# BANK_3.net
KiCad netlist of a schematic drawn in Altium Designer
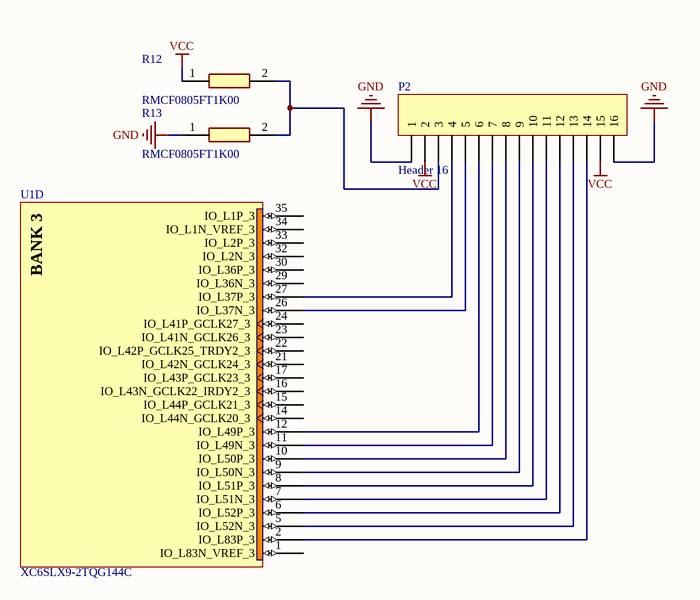
[diagram p0: BANK_3.SchDoc]

(export (version "E")
  (design (tool "Eeschema 10.0.6"))
  (components
    (comp (ref "P2")
      (value "Header 16")
      (footprint "HDR1X16")
      (description "Header, 16-Pin")
      (fields (field (name "PUBLISHER") "Altium Limited"))
      (libsource (lib "Schlib1_FPGA") (part "Header 16"))
    )
    (comp (ref "R12")
      (value "RMCF0805FT1K00")
      (footprint "PcbLib1:RESC2012X65N")
      (description "Resistor")
      (fields (field (name "MF") "Stackpole Electronics Inc"))
      (libsource (lib "Schlib1_FPGA") (part "RES 1K OHM 1% 1/8W 0805"))
    )
    (comp (ref "R13")
      (value "RMCF0805FT1K00")
      (footprint "PcbLib1:RESC2012X65N")
      (description "Resistor")
      (fields (field (name "MF") "Stackpole Electronics Inc"))
      (libsource (lib "Schlib1_FPGA") (part "RES 1K OHM 1% 1/8W 0805"))
    )
    (comp (ref "U1")
      (value "XC6SLX9-2TQG144C")
      (footprint "TQG144_N")
      (libsource (lib "Xilinx Spartan-6") (part "XC6SLX9-2TQG144C"))
    )
  )
  (nets
    (net (code "1") (name "GND") (class "Default")
      (node (ref "P2") (pin "1") (pinfunction "1_1") (pintype "passive"))
      (node (ref "P2") (pin "16") (pinfunction "16_16") (pintype "passive"))
      (node (ref "R13") (pin "1") (pinfunction "1_1") (pintype "passive"))
    )
    (net (code "2") (name "Net-(P2-Pad3)") (class "Default")
      (node (ref "P2") (pin "3") (pinfunction "3_3") (pintype "passive"))
      (node (ref "R12") (pin "2") (pinfunction "2_2") (pintype "passive"))
      (node (ref "R13") (pin "2") (pinfunction "2_2") (pintype "passive"))
    )
    (net (code "3") (name "Net-(U1D-IO_L37N_3)") (class "Default")
      (node (ref "P2") (pin "5") (pinfunction "5_5") (pintype "passive"))
      (node (ref "U1") (pin "26") (pinfunction "IO_L37N_3_26") (pintype "bidirectional"))
    )
    (net (code "4") (name "Net-(U1D-IO_L37P_3)") (class "Default")
      (node (ref "P2") (pin "4") (pinfunction "4_4") (pintype "passive"))
      (node (ref "U1") (pin "27") (pinfunction "IO_L37P_3_27") (pintype "bidirectional"))
    )
    (net (code "5") (name "Net-(U1D-IO_L49N_3)") (class "Default")
      (node (ref "P2") (pin "7") (pinfunction "7_7") (pintype "passive"))
      (node (ref "U1") (pin "11") (pinfunction "IO_L49N_3_11") (pintype "bidirectional"))
    )
    (net (code "6") (name "Net-(U1D-IO_L49P_3)") (class "Default")
      (node (ref "P2") (pin "6") (pinfunction "6_6") (pintype "passive"))
      (node (ref "U1") (pin "12") (pinfunction "IO_L49P_3_12") (pintype "bidirectional"))
    )
    (net (code "7") (name "Net-(U1D-IO_L50N_3)") (class "Default")
      (node (ref "P2") (pin "9") (pinfunction "9_9") (pintype "passive"))
      (node (ref "U1") (pin "9") (pinfunction "IO_L50N_3_9") (pintype "bidirectional"))
    )
    (net (code "8") (name "Net-(U1D-IO_L50P_3)") (class "Default")
      (node (ref "P2") (pin "8") (pinfunction "8_8") (pintype "passive"))
      (node (ref "U1") (pin "10") (pinfunction "IO_L50P_3_10") (pintype "bidirectional"))
    )
    (net (code "9") (name "Net-(U1D-IO_L51N_3)") (class "Default")
      (node (ref "P2") (pin "11") (pinfunction "11_11") (pintype "passive"))
      (node (ref "U1") (pin "7") (pinfunction "IO_L51N_3_7") (pintype "bidirectional"))
    )
    (net (code "10") (name "Net-(U1D-IO_L51P_3)") (class "Default")
      (node (ref "P2") (pin "10") (pinfunction "10_10") (pintype "passive"))
      (node (ref "U1") (pin "8") (pinfunction "IO_L51P_3_8") (pintype "bidirectional"))
    )
    (net (code "11") (name "Net-(U1D-IO_L52N_3)") (class "Default")
      (node (ref "P2") (pin "13") (pinfunction "13_13") (pintype "passive"))
      (node (ref "U1") (pin "5") (pinfunction "IO_L52N_3_5") (pintype "bidirectional"))
    )
    (net (code "12") (name "Net-(U1D-IO_L52P_3)") (class "Default")
      (node (ref "P2") (pin "12") (pinfunction "12_12") (pintype "passive"))
      (node (ref "U1") (pin "6") (pinfunction "IO_L52P_3_6") (pintype "bidirectional"))
    )
    (net (code "13") (name "Net-(U1D-IO_L83P_3)") (class "Default")
      (node (ref "P2") (pin "14") (pinfunction "14_14") (pintype "passive"))
      (node (ref "U1") (pin "2") (pinfunction "IO_L83P_3_2") (pintype "bidirectional"))
    )
    (net (code "14") (name "VCC") (class "Default")
      (node (ref "P2") (pin "15") (pinfunction "15_15") (pintype "passive"))
      (node (ref "P2") (pin "2") (pinfunction "2_2") (pintype "passive"))
      (node (ref "R12") (pin "1") (pinfunction "1_1") (pintype "passive"))
    )
    (net (code "15") (name "unconnected-(U1D-IO_L1N_VREF_3-Pad34)") (class "Default")
      (node (ref "U1") (pin "34") (pinfunction "IO_L1N_VREF_3_34") (pintype "bidirectional"))
    )
    (net (code "16") (name "unconnected-(U1D-IO_L1P_3-Pad35)") (class "Default")
      (node (ref "U1") (pin "35") (pinfunction "IO_L1P_3_35") (pintype "bidirectional"))
    )
    (net (code "17") (name "unconnected-(U1D-IO_L2N_3-Pad32)") (class "Default")
      (node (ref "U1") (pin "32") (pinfunction "IO_L2N_3_32") (pintype "bidirectional"))
    )
    (net (code "18") (name "unconnected-(U1D-IO_L2P_3-Pad33)") (class "Default")
      (node (ref "U1") (pin "33") (pinfunction "IO_L2P_3_33") (pintype "bidirectional"))
    )
    (net (code "19") (name "unconnected-(U1D-IO_L36N_3-Pad29)") (class "Default")
      (node (ref "U1") (pin "29") (pinfunction "IO_L36N_3_29") (pintype "bidirectional"))
    )
    (net (code "20") (name "unconnected-(U1D-IO_L36P_3-Pad30)") (class "Default")
      (node (ref "U1") (pin "30") (pinfunction "IO_L36P_3_30") (pintype "bidirectional"))
    )
    (net (code "21") (name "unconnected-(U1D-IO_L41N_GCLK26_3-Pad23)") (class "Default")
      (node (ref "U1") (pin "23") (pinfunction "IO_L41N_GCLK26_3_23") (pintype "bidirectional"))
    )
    (net (code "22") (name "unconnected-(U1D-IO_L41P_GCLK27_3-Pad24)") (class "Default")
      (node (ref "U1") (pin "24") (pinfunction "IO_L41P_GCLK27_3_24") (pintype "bidirectional"))
    )
    (net (code "23") (name "unconnected-(U1D-IO_L42N_GCLK24_3-Pad21)") (class "Default")
      (node (ref "U1") (pin "21") (pinfunction "IO_L42N_GCLK24_3_21") (pintype "bidirectional"))
    )
    (net (code "24") (name "unconnected-(U1D-IO_L42P_GCLK25_TRDY2_3-Pad22)") (class "Default")
      (node (ref "U1") (pin "22") (pinfunction "IO_L42P_GCLK25_TRDY2_3_22") (pintype "bidirectional"))
    )
    (net (code "25") (name "unconnected-(U1D-IO_L43N_GCLK22_IRDY2_3-Pad16)") (class "Default")
      (node (ref "U1") (pin "16") (pinfunction "IO_L43N_GCLK22_IRDY2_3_16") (pintype "bidirectional"))
    )
    (net (code "26") (name "unconnected-(U1D-IO_L43P_GCLK23_3-Pad17)") (class "Default")
      (node (ref "U1") (pin "17") (pinfunction "IO_L43P_GCLK23_3_17") (pintype "bidirectional"))
    )
    (net (code "27") (name "unconnected-(U1D-IO_L44N_GCLK20_3-Pad14)") (class "Default")
      (node (ref "U1") (pin "14") (pinfunction "IO_L44N_GCLK20_3_14") (pintype "bidirectional"))
    )
    (net (code "28") (name "unconnected-(U1D-IO_L44P_GCLK21_3-Pad15)") (class "Default")
      (node (ref "U1") (pin "15") (pinfunction "IO_L44P_GCLK21_3_15") (pintype "bidirectional"))
    )
    (net (code "29") (name "unconnected-(U1D-IO_L83N_VREF_3-Pad1)") (class "Default")
      (node (ref "U1") (pin "1") (pinfunction "IO_L83N_VREF_3_1") (pintype "bidirectional"))
    )
  )
)
